# power_breakout_v1.net
KiCad netlist of a schematic drawn in EAGLE
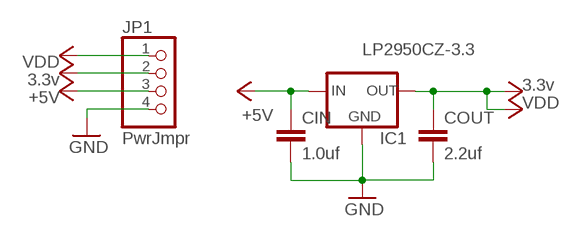
[diagram p0: schematic, sheet 1]

(export (version "E")
  (design (tool "Eeschema 10.0.6"))
  (components
    (comp (ref "CIN")
      (value "1.0uf")
      (footprint "eagle-import:C025-025X050")
      (libsource (lib "eagle-import") (part "C-EU025-025X050"))
    )
    (comp (ref "COUT")
      (value "2.2uf")
      (footprint "eagle-import:C025-025X050")
      (libsource (lib "eagle-import") (part "C-EU025-025X050"))
    )
    (comp (ref "IC1")
      (value "LP2950CZ-3.3")
      (footprint "eagle-import:TO92")
      (libsource (lib "eagle-import") (part "LP2950?CZ-3.3"))
    )
    (comp (ref "JP1")
      (value "PwrJmpr")
      (footprint "eagle-import:1X04")
      (libsource (lib "eagle-import") (part "PINHD-1X4"))
    )
  )
  (nets
    (net (code "1") (name "+5V") (class "Default")
      (node (ref "CIN") (pin "1") (pinfunction "1_1") (pintype "passive"))
      (node (ref "IC1") (pin "3") (pinfunction "IN_3") (pintype "input"))
      (node (ref "JP1") (pin "3") (pinfunction "3_3") (pintype "passive"))
    )
    (net (code "2") (name "3.3v") (class "Default")
      (node (ref "COUT") (pin "1") (pinfunction "1_1") (pintype "passive"))
      (node (ref "IC1") (pin "1") (pinfunction "OUT_1") (pintype "passive"))
      (node (ref "JP1") (pin "1") (pinfunction "1_1") (pintype "passive"))
      (node (ref "JP1") (pin "2") (pinfunction "2_2") (pintype "passive"))
    )
    (net (code "3") (name "GND") (class "Default")
      (node (ref "CIN") (pin "2") (pinfunction "2_2") (pintype "passive"))
      (node (ref "COUT") (pin "2") (pinfunction "2_2") (pintype "passive"))
      (node (ref "IC1") (pin "2") (pinfunction "GND_2") (pintype "input"))
      (node (ref "JP1") (pin "4") (pinfunction "4_4") (pintype "passive"))
    )
  )
)
